# 1-Schematic_reverse_polarity_protection.net
KiCad netlist of a schematic drawn in EasyEDA
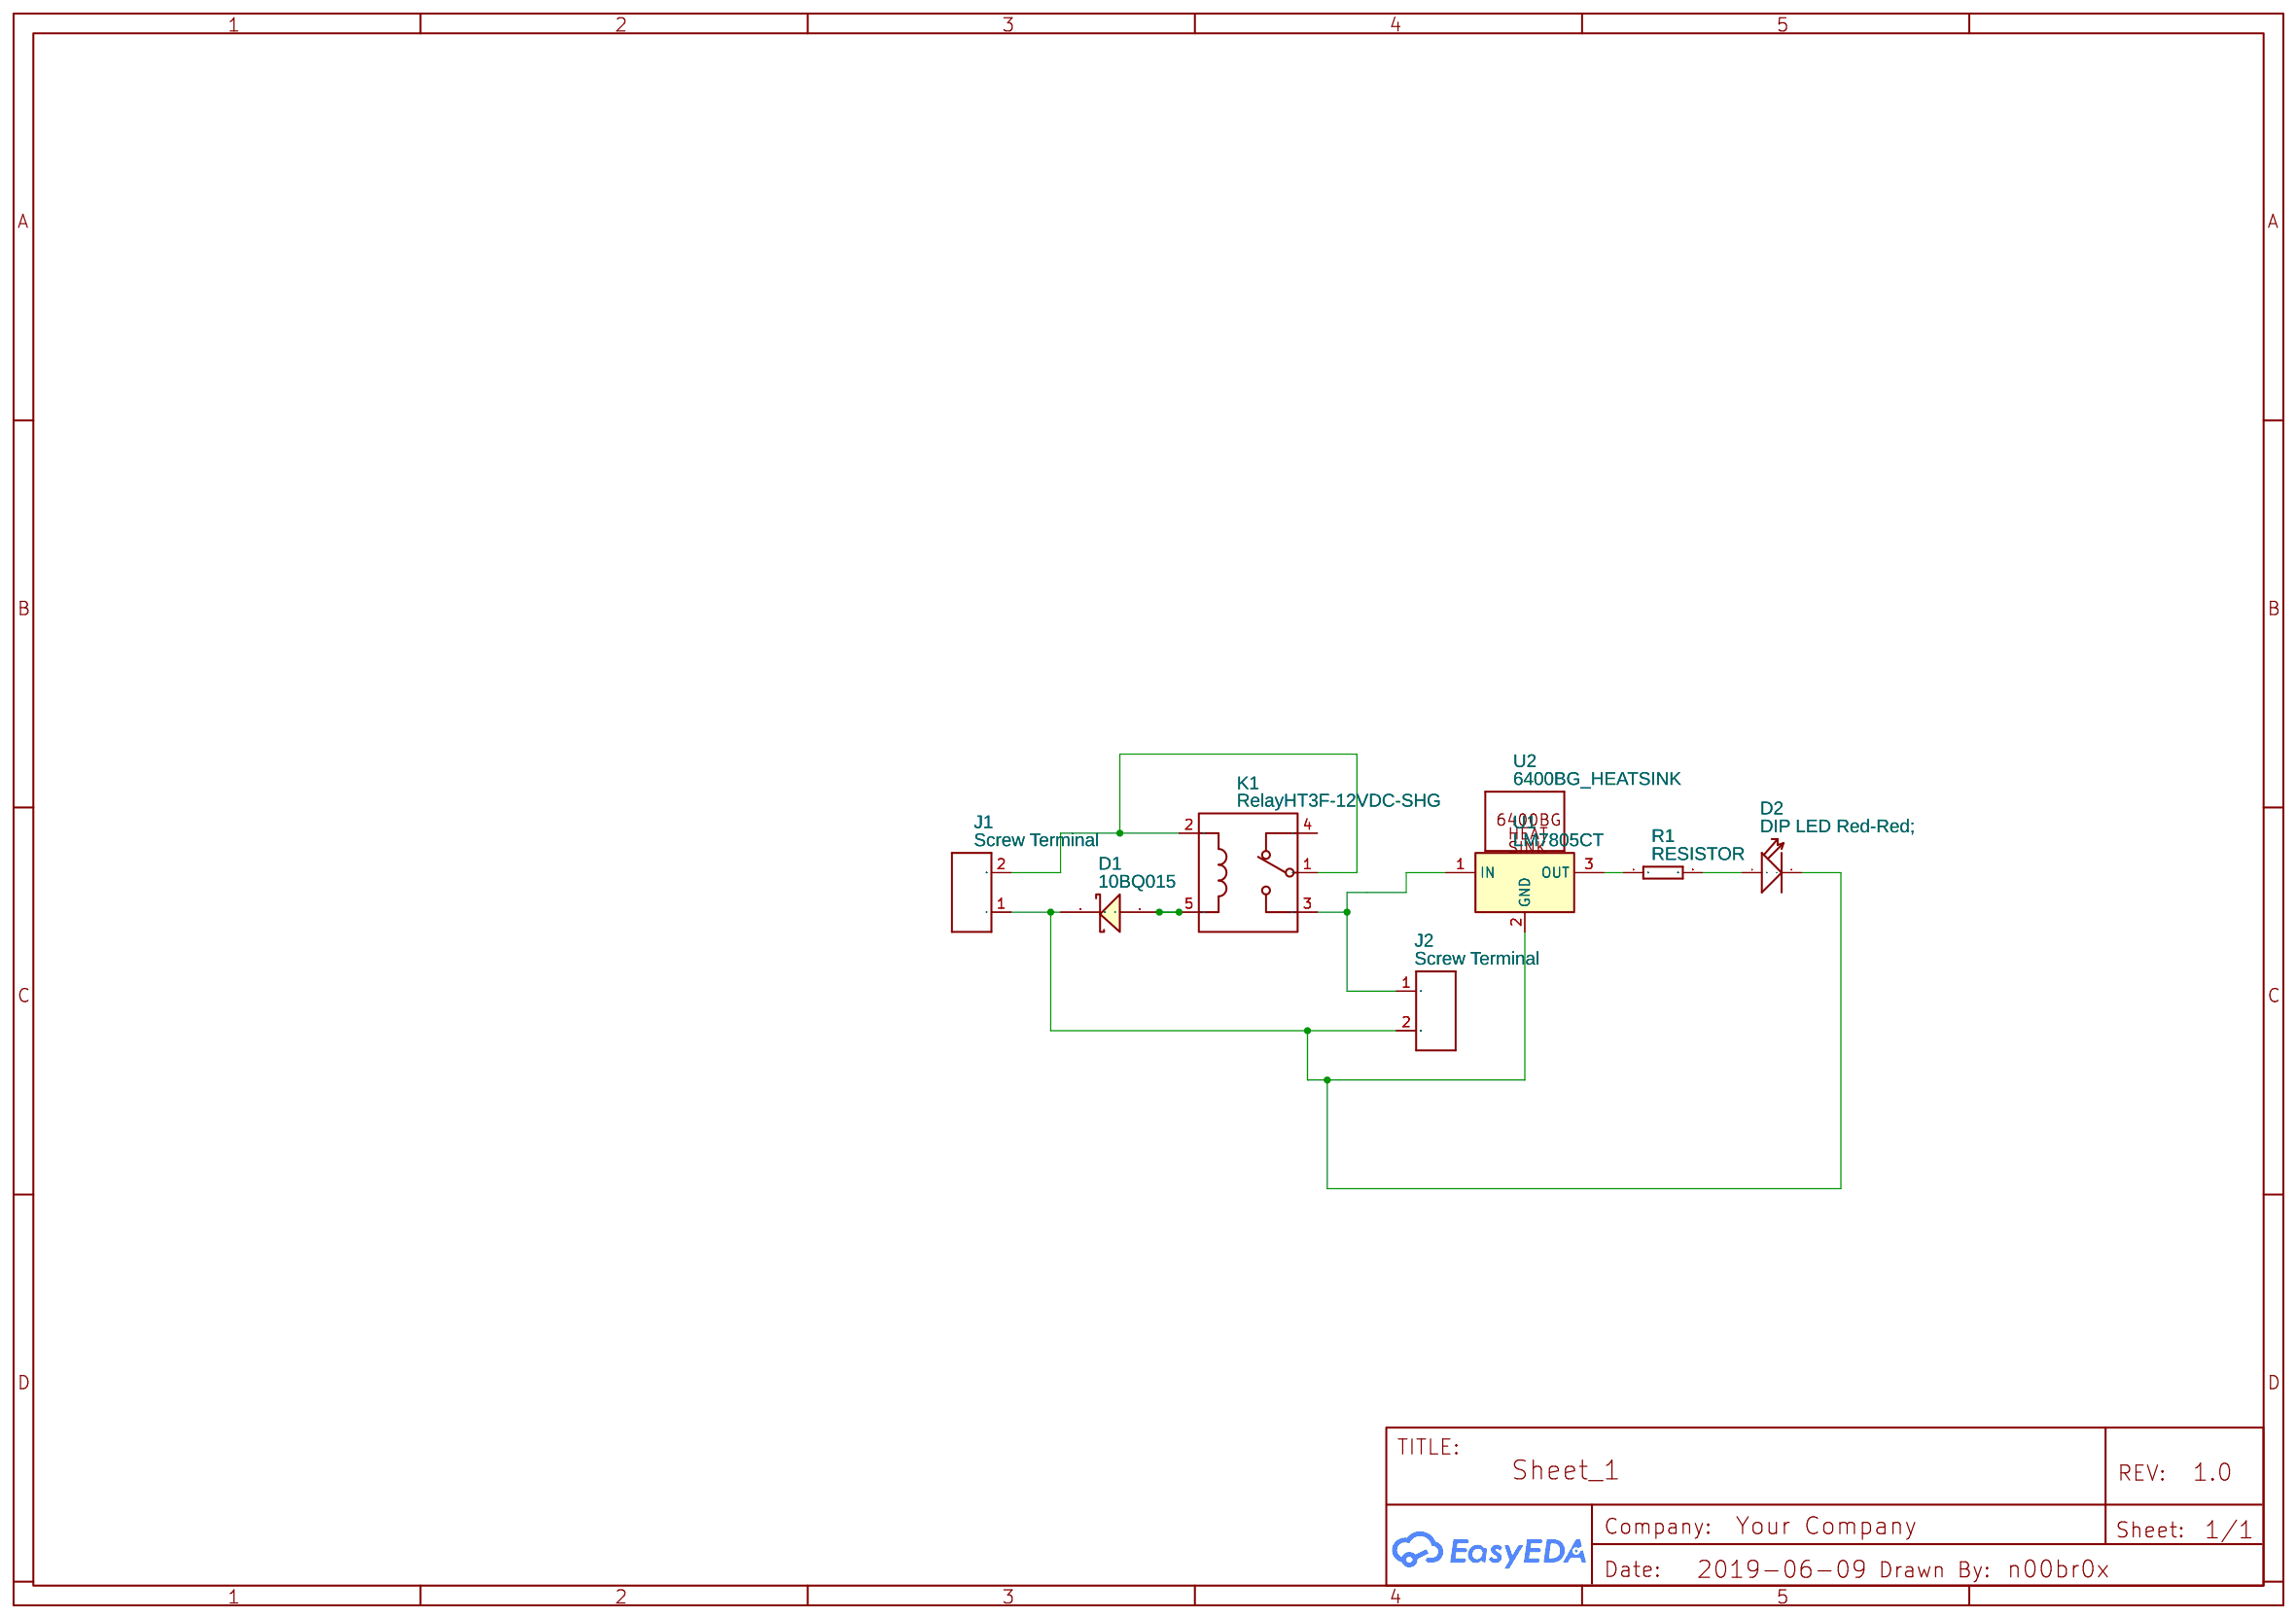
[diagram p0: schematic sheet]

(export (version "E")
  (design (tool "Eeschema 10.0.6"))
  (components
    (comp (ref "D1")
      (value "10BQ015")
      (fields (field (name "BOM_Manufacturer Part") "?"))
      (libsource (lib "") (part "Unknown_555_455"))
    )
    (comp (ref "D2")
      (value "DIP LED Red-Red;")
      (fields (field (name "BOM_Manufacturer Part") "?"))
      (libsource (lib "") (part "Unknown_890_430"))
    )
    (comp (ref "J1")
      (value "Screw Terminal")
      (fields (field (name "BOM_Manufacturer Part") "?"))
      (libsource (lib "") (part "Unknown_490_445"))
    )
    (comp (ref "J2")
      (value "Screw Terminal")
      (fields (field (name "BOM_Manufacturer Part") "?"))
      (libsource (lib "") (part "Unknown_715_505"))
    )
    (comp (ref "K1")
      (value "RelayHT3F-12VDC-SHG")
      (fields (field (name "BOM_Supplier Part") "C22022"))
      (libsource (lib "") (part "Unknown_630_435"))
    )
    (comp (ref "R1")
      (value "RESISTOR")
      (fields (field (name "BOM_Manufacturer Part") "?"))
      (libsource (lib "") (part "Unknown_835_435"))
    )
    (comp (ref "U1")
      (value "LM7805CT")
      (fields (field (name "BOM_Manufacturer Part") "?"))
      (libsource (lib "") (part "Unknown_740_435"))
    )
    (comp (ref "U2")
      (value "6400BG_HEATSINK")
      (fields (field (name "BOM_Manufacturer Part") "?"))
      (libsource (lib "") (part "Unknown_765_410"))
    )
  )
  (nets
    (net (code "1") (name "Net-(D1-A)") (class "Default")
      (node (ref "D1") (pin "1") (pinfunction "A_1") (pintype "unspecified"))
      (node (ref "K1") (pin "5") (pinfunction "5_5") (pintype "unspecified"))
    )
    (net (code "2") (name "Net-(D1-K)") (class "Default")
      (node (ref "D1") (pin "2") (pinfunction "K_2") (pintype "unspecified"))
      (node (ref "D2") (pin "K") (pinfunction "-_K") (pintype "unspecified"))
      (node (ref "J1") (pin "1") (pinfunction "1_1") (pintype "unspecified"))
      (node (ref "J2") (pin "2") (pinfunction "2_2") (pintype "unspecified"))
      (node (ref "U1") (pin "2") (pinfunction "GND_2") (pintype "bidirectional"))
    )
    (net (code "3") (name "Net-(D2-+)") (class "Default")
      (node (ref "D2") (pin "A") (pinfunction "+_A") (pintype "unspecified"))
      (node (ref "R1") (pin "2") (pinfunction "2_2") (pintype "unspecified"))
    )
    (net (code "4") (name "Net-(J1-Pad2)") (class "Default")
      (node (ref "J1") (pin "2") (pinfunction "2_2") (pintype "unspecified"))
      (node (ref "K1") (pin "1") (pinfunction "1_1") (pintype "unspecified"))
      (node (ref "K1") (pin "2") (pinfunction "2_2") (pintype "unspecified"))
    )
    (net (code "5") (name "Net-(U1-IN)") (class "Default")
      (node (ref "J2") (pin "1") (pinfunction "1_1") (pintype "unspecified"))
      (node (ref "K1") (pin "3") (pinfunction "3_3") (pintype "unspecified"))
      (node (ref "U1") (pin "1") (pinfunction "IN_1") (pintype "input"))
    )
    (net (code "6") (name "Net-(U1-OUT)") (class "Default")
      (node (ref "R1") (pin "1") (pinfunction "1_1") (pintype "unspecified"))
      (node (ref "U1") (pin "3") (pinfunction "OUT_3") (pintype "bidirectional"))
    )
    (net (code "7") (name "unconnected-(K1-Pad4)") (class "Default")
      (node (ref "K1") (pin "4") (pinfunction "4_4") (pintype "unspecified"))
    )
  )
)
